# Sensor_Board_A.net
KiCad netlist of a schematic drawn in EAGLE
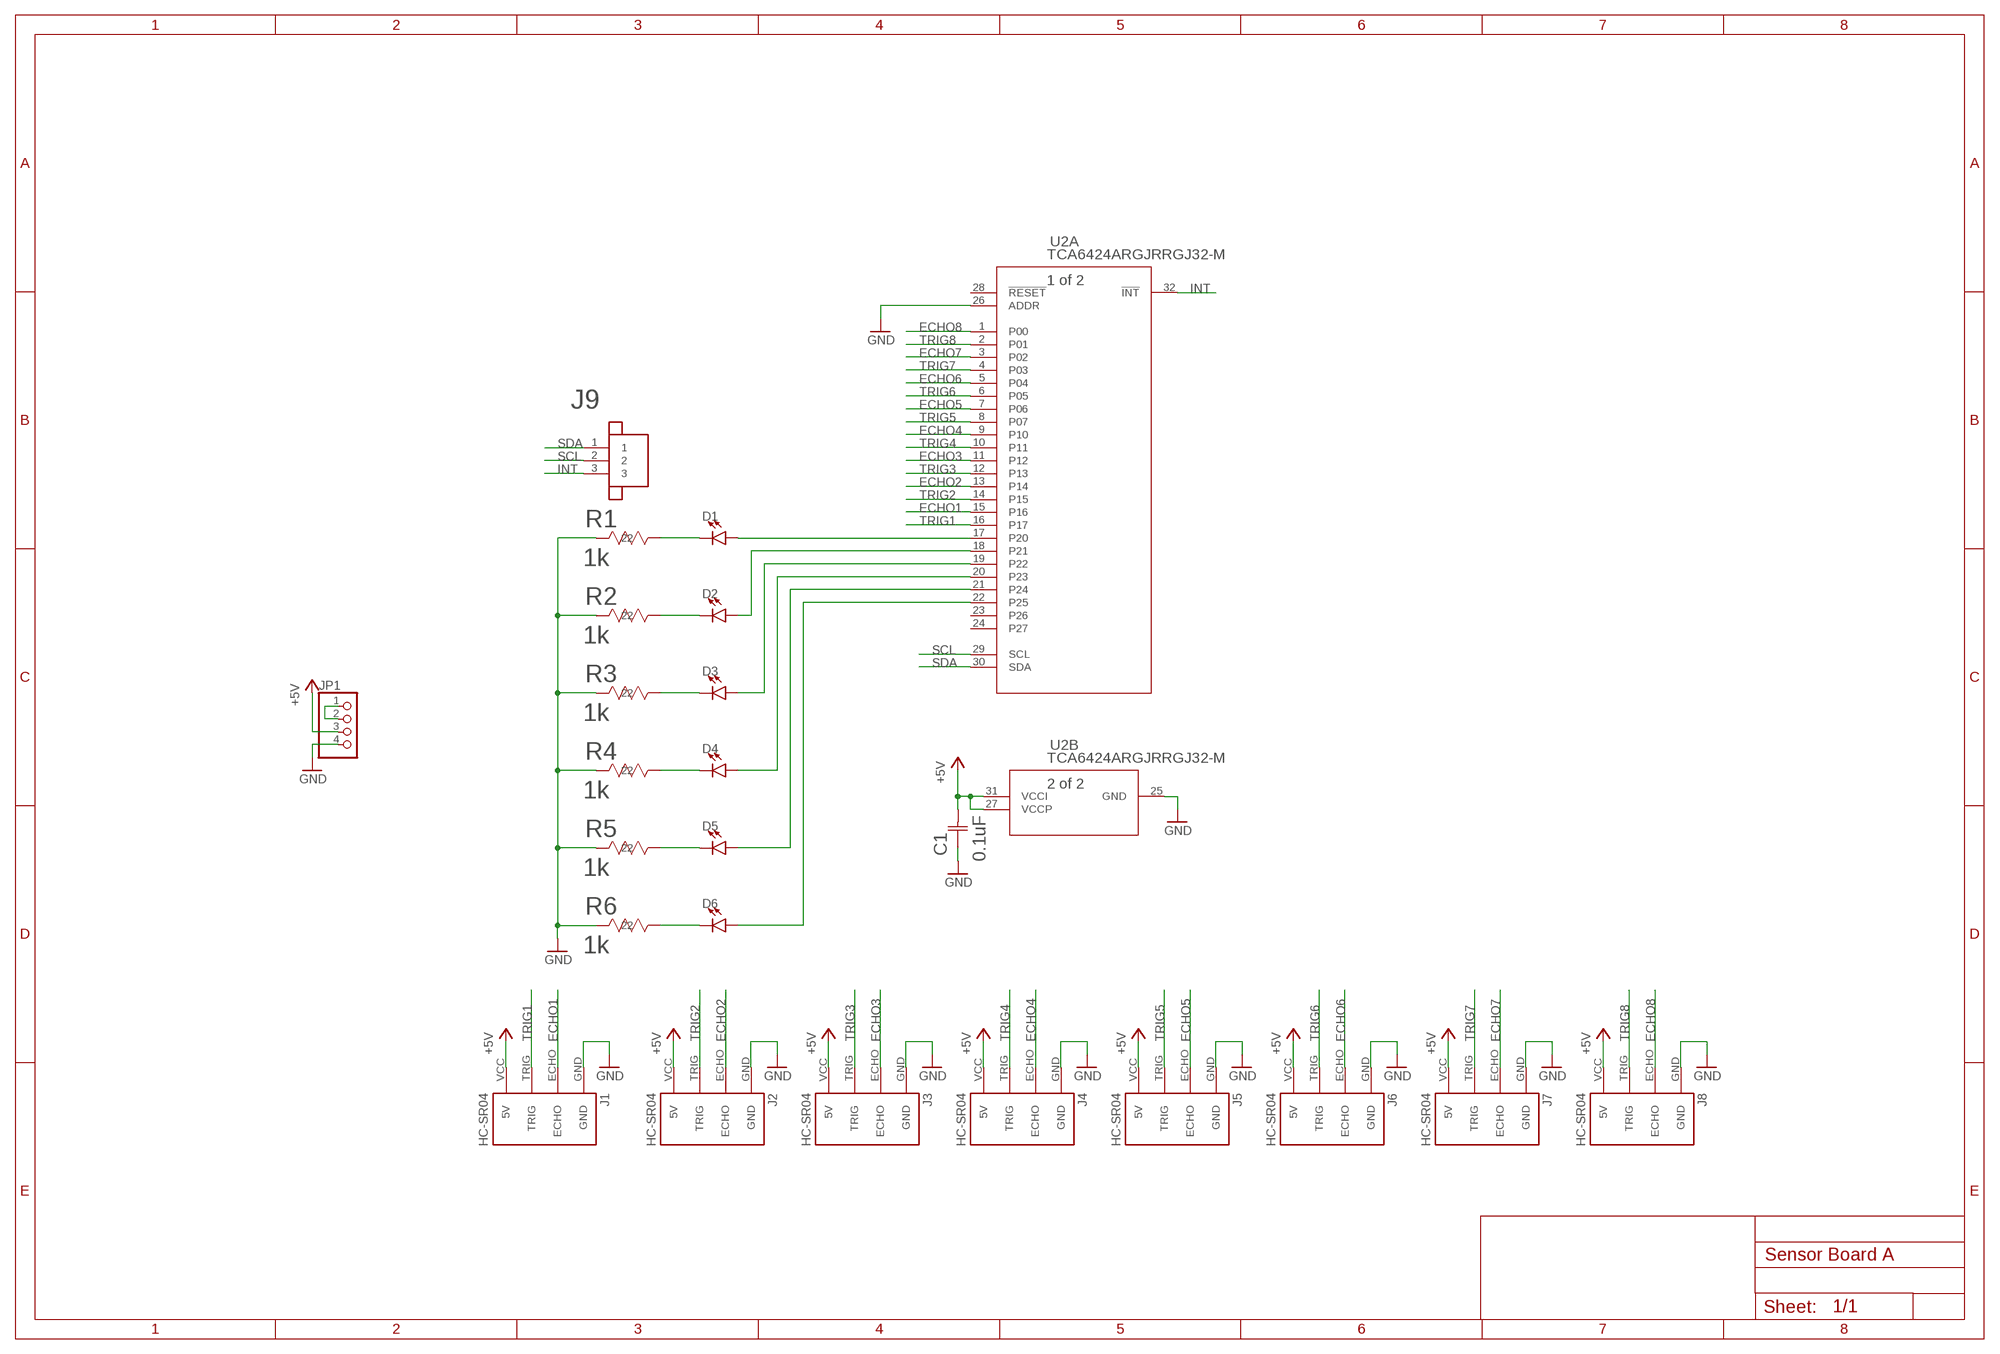
[diagram p0: schematic, sheet 1]

(export (version "E")
  (design (tool "Eeschema 10.0.6"))
  (components
    (comp (ref "C1")
      (value "0.1uF")
      (footprint "eagle-import:0805")
      (fields
        (field (name "MANUFACTURER_PART_NUMBER") "08055C104KAT2A")
        (field (name "COPYRIGHT") "Copyright C 2015 Accelerated Designs. All rights reserved")
      )
      (libsource (lib "eagle-import") (part "08055C104KAT2A"))
    )
    (comp (ref "D1")
      (value "LED0603")
      (footprint "eagle-import:LED-0603")
      (libsource (lib "eagle-import") (part "LED0603"))
    )
    (comp (ref "D2")
      (value "LED0603")
      (footprint "eagle-import:LED-0603")
      (libsource (lib "eagle-import") (part "LED0603"))
    )
    (comp (ref "D3")
      (value "LED0603")
      (footprint "eagle-import:LED-0603")
      (libsource (lib "eagle-import") (part "LED0603"))
    )
    (comp (ref "D4")
      (value "LED0603")
      (footprint "eagle-import:LED-0603")
      (libsource (lib "eagle-import") (part "LED0603"))
    )
    (comp (ref "D5")
      (value "LED0603")
      (footprint "eagle-import:LED-0603")
      (libsource (lib "eagle-import") (part "LED0603"))
    )
    (comp (ref "D6")
      (value "LED0603")
      (footprint "eagle-import:LED-0603")
      (libsource (lib "eagle-import") (part "LED0603"))
    )
    (comp (ref "J1")
      (value "HC-SR04")
      (footprint "eagle-import:HC-SR04_FOOTPRINT")
      (libsource (lib "eagle-import") (part "HC-SR04"))
    )
    (comp (ref "J2")
      (value "HC-SR04")
      (footprint "eagle-import:HC-SR04_FOOTPRINT")
      (libsource (lib "eagle-import") (part "HC-SR04"))
    )
    (comp (ref "J3")
      (value "HC-SR04")
      (footprint "eagle-import:HC-SR04_FOOTPRINT")
      (libsource (lib "eagle-import") (part "HC-SR04"))
    )
    (comp (ref "J4")
      (value "HC-SR04")
      (footprint "eagle-import:HC-SR04_FOOTPRINT")
      (libsource (lib "eagle-import") (part "HC-SR04"))
    )
    (comp (ref "J5")
      (value "HC-SR04")
      (footprint "eagle-import:HC-SR04_FOOTPRINT")
      (libsource (lib "eagle-import") (part "HC-SR04"))
    )
    (comp (ref "J6")
      (value "HC-SR04")
      (footprint "eagle-import:HC-SR04_FOOTPRINT")
      (libsource (lib "eagle-import") (part "HC-SR04"))
    )
    (comp (ref "J7")
      (value "HC-SR04")
      (footprint "eagle-import:HC-SR04_FOOTPRINT")
      (libsource (lib "eagle-import") (part "HC-SR04"))
    )
    (comp (ref "J8")
      (value "HC-SR04")
      (footprint "eagle-import:HC-SR04_FOOTPRINT")
      (libsource (lib "eagle-import") (part "HC-SR04"))
    )
    (comp (ref "J9")
      (value "JST_SH_3POS")
      (footprint "eagle-import:JST_SH_3POS")
      (libsource (lib "eagle-import") (part "JST_SH_3POS"))
    )
    (comp (ref "JP1")
      (value "PINHD-1X4")
      (footprint "eagle-import:1X04")
      (libsource (lib "eagle-import") (part "PINHD-1X4"))
    )
    (comp (ref "R1")
      (value "1k")
      (footprint "eagle-import:RC0603N-M")
      (fields
        (field (name "DIGIKEYPARTNUMBER") "3111.0KGRTRND")
        (field (name "MANUFACTURER_PART_NUMBER") "RC0603JR071KL")
        (field (name "NEWARKPARTNUMBER") "14M7231")
        (field (name "COPYRIGHT") "Copyright C 2015 Accelerated Designs. All rights reserved")
      )
      (libsource (lib "eagle-import") (part "RC0603JR-071KLRC0603N-M"))
    )
    (comp (ref "R2")
      (value "1k")
      (footprint "eagle-import:RC0603N-M")
      (fields
        (field (name "DIGIKEYPARTNUMBER") "3111.0KGRTRND")
        (field (name "MANUFACTURER_PART_NUMBER") "RC0603JR071KL")
        (field (name "NEWARKPARTNUMBER") "14M7231")
        (field (name "COPYRIGHT") "Copyright C 2015 Accelerated Designs. All rights reserved")
      )
      (libsource (lib "eagle-import") (part "RC0603JR-071KLRC0603N-M"))
    )
    (comp (ref "R3")
      (value "1k")
      (footprint "eagle-import:RC0603N-M")
      (fields
        (field (name "DIGIKEYPARTNUMBER") "3111.0KGRTRND")
        (field (name "MANUFACTURER_PART_NUMBER") "RC0603JR071KL")
        (field (name "NEWARKPARTNUMBER") "14M7231")
        (field (name "COPYRIGHT") "Copyright C 2015 Accelerated Designs. All rights reserved")
      )
      (libsource (lib "eagle-import") (part "RC0603JR-071KLRC0603N-M"))
    )
    (comp (ref "R4")
      (value "1k")
      (footprint "eagle-import:RC0603N-M")
      (fields
        (field (name "DIGIKEYPARTNUMBER") "3111.0KGRTRND")
        (field (name "MANUFACTURER_PART_NUMBER") "RC0603JR071KL")
        (field (name "NEWARKPARTNUMBER") "14M7231")
        (field (name "COPYRIGHT") "Copyright C 2015 Accelerated Designs. All rights reserved")
      )
      (libsource (lib "eagle-import") (part "RC0603JR-071KLRC0603N-M"))
    )
    (comp (ref "R5")
      (value "1k")
      (footprint "eagle-import:RC0603N-M")
      (fields
        (field (name "DIGIKEYPARTNUMBER") "3111.0KGRTRND")
        (field (name "MANUFACTURER_PART_NUMBER") "RC0603JR071KL")
        (field (name "NEWARKPARTNUMBER") "14M7231")
        (field (name "COPYRIGHT") "Copyright C 2015 Accelerated Designs. All rights reserved")
      )
      (libsource (lib "eagle-import") (part "RC0603JR-071KLRC0603N-M"))
    )
    (comp (ref "R6")
      (value "1k")
      (footprint "eagle-import:RC0603N-M")
      (fields
        (field (name "DIGIKEYPARTNUMBER") "3111.0KGRTRND")
        (field (name "MANUFACTURER_PART_NUMBER") "RC0603JR071KL")
        (field (name "NEWARKPARTNUMBER") "14M7231")
        (field (name "COPYRIGHT") "Copyright C 2015 Accelerated Designs. All rights reserved")
      )
      (libsource (lib "eagle-import") (part "RC0603JR-071KLRC0603N-M"))
    )
    (comp (ref "U2")
      (value "TCA6424ARGJRRGJ32-M")
      (footprint "eagle-import:RGJ32-M")
      (fields (field (name "MANUFACTURER_PART_NUMBER") "TCA6424ARGJR"))
      (libsource (lib "eagle-import") (part "TCA6424ARGJRRGJ32-M"))
    )
  )
  (nets
    (net (code "1") (name "+5V") (class "Default")
      (node (ref "C1") (pin "2") (pinfunction "2_2") (pintype "passive"))
      (node (ref "J1") (pin "VCC") (pinfunction "5V_VCC") (pintype "bidirectional"))
      (node (ref "J2") (pin "VCC") (pinfunction "5V_VCC") (pintype "bidirectional"))
      (node (ref "J3") (pin "VCC") (pinfunction "5V_VCC") (pintype "bidirectional"))
      (node (ref "J4") (pin "VCC") (pinfunction "5V_VCC") (pintype "bidirectional"))
      (node (ref "J5") (pin "VCC") (pinfunction "5V_VCC") (pintype "bidirectional"))
      (node (ref "J6") (pin "VCC") (pinfunction "5V_VCC") (pintype "bidirectional"))
      (node (ref "J7") (pin "VCC") (pinfunction "5V_VCC") (pintype "bidirectional"))
      (node (ref "J8") (pin "VCC") (pinfunction "5V_VCC") (pintype "bidirectional"))
      (node (ref "JP1") (pin "3") (pinfunction "3_3") (pintype "passive"))
      (node (ref "U2") (pin "27") (pinfunction "VCCP_27") (pintype "power_in"))
      (node (ref "U2") (pin "31") (pinfunction "VCCI_31") (pintype "power_in"))
    )
    (net (code "2") (name "/ECHO1") (class "Default")
      (node (ref "J1") (pin "ECHO") (pinfunction "ECHO_ECHO") (pintype "bidirectional"))
      (node (ref "U2") (pin "15") (pinfunction "P16_15") (pintype "input"))
    )
    (net (code "3") (name "/ECHO2") (class "Default")
      (node (ref "J2") (pin "ECHO") (pinfunction "ECHO_ECHO") (pintype "bidirectional"))
      (node (ref "U2") (pin "13") (pinfunction "P14_13") (pintype "input"))
    )
    (net (code "4") (name "/ECHO3") (class "Default")
      (node (ref "J3") (pin "ECHO") (pinfunction "ECHO_ECHO") (pintype "bidirectional"))
      (node (ref "U2") (pin "11") (pinfunction "P12_11") (pintype "input"))
    )
    (net (code "5") (name "/ECHO4") (class "Default")
      (node (ref "J4") (pin "ECHO") (pinfunction "ECHO_ECHO") (pintype "bidirectional"))
      (node (ref "U2") (pin "9") (pinfunction "P10_9") (pintype "input"))
    )
    (net (code "6") (name "/ECHO5") (class "Default")
      (node (ref "J5") (pin "ECHO") (pinfunction "ECHO_ECHO") (pintype "bidirectional"))
      (node (ref "U2") (pin "7") (pinfunction "P06_7") (pintype "input"))
    )
    (net (code "7") (name "/ECHO6") (class "Default")
      (node (ref "J6") (pin "ECHO") (pinfunction "ECHO_ECHO") (pintype "bidirectional"))
      (node (ref "U2") (pin "5") (pinfunction "P04_5") (pintype "input"))
    )
    (net (code "8") (name "/ECHO7") (class "Default")
      (node (ref "J7") (pin "ECHO") (pinfunction "ECHO_ECHO") (pintype "bidirectional"))
      (node (ref "U2") (pin "3") (pinfunction "P02_3") (pintype "input"))
    )
    (net (code "9") (name "/ECHO8") (class "Default")
      (node (ref "J8") (pin "ECHO") (pinfunction "ECHO_ECHO") (pintype "bidirectional"))
      (node (ref "U2") (pin "1") (pinfunction "P00_1") (pintype "input"))
    )
    (net (code "10") (name "/INT") (class "Default")
      (node (ref "J9") (pin "3") (pinfunction "3_3") (pintype "bidirectional"))
      (node (ref "U2") (pin "32") (pinfunction "~{INT}_32") (pintype "output"))
    )
    (net (code "11") (name "/SCL") (class "Default")
      (node (ref "J9") (pin "2") (pinfunction "2_2") (pintype "bidirectional"))
      (node (ref "U2") (pin "29") (pinfunction "SCL_29") (pintype "passive"))
    )
    (net (code "12") (name "/SDA") (class "Default")
      (node (ref "J9") (pin "1") (pinfunction "1_1") (pintype "bidirectional"))
      (node (ref "U2") (pin "30") (pinfunction "SDA_30") (pintype "passive"))
    )
    (net (code "13") (name "/TRIG1") (class "Default")
      (node (ref "J1") (pin "TRIG") (pinfunction "TRIG_TRIG") (pintype "bidirectional"))
      (node (ref "U2") (pin "16") (pinfunction "P17_16") (pintype "input"))
    )
    (net (code "14") (name "/TRIG2") (class "Default")
      (node (ref "J2") (pin "TRIG") (pinfunction "TRIG_TRIG") (pintype "bidirectional"))
      (node (ref "U2") (pin "14") (pinfunction "P15_14") (pintype "input"))
    )
    (net (code "15") (name "/TRIG3") (class "Default")
      (node (ref "J3") (pin "TRIG") (pinfunction "TRIG_TRIG") (pintype "bidirectional"))
      (node (ref "U2") (pin "12") (pinfunction "P13_12") (pintype "input"))
    )
    (net (code "16") (name "/TRIG4") (class "Default")
      (node (ref "J4") (pin "TRIG") (pinfunction "TRIG_TRIG") (pintype "bidirectional"))
      (node (ref "U2") (pin "10") (pinfunction "P11_10") (pintype "input"))
    )
    (net (code "17") (name "/TRIG5") (class "Default")
      (node (ref "J5") (pin "TRIG") (pinfunction "TRIG_TRIG") (pintype "bidirectional"))
      (node (ref "U2") (pin "8") (pinfunction "P07_8") (pintype "input"))
    )
    (net (code "18") (name "/TRIG6") (class "Default")
      (node (ref "J6") (pin "TRIG") (pinfunction "TRIG_TRIG") (pintype "bidirectional"))
      (node (ref "U2") (pin "6") (pinfunction "P05_6") (pintype "input"))
    )
    (net (code "19") (name "/TRIG7") (class "Default")
      (node (ref "J7") (pin "TRIG") (pinfunction "TRIG_TRIG") (pintype "bidirectional"))
      (node (ref "U2") (pin "4") (pinfunction "P03_4") (pintype "input"))
    )
    (net (code "20") (name "/TRIG8") (class "Default")
      (node (ref "J8") (pin "TRIG") (pinfunction "TRIG_TRIG") (pintype "bidirectional"))
      (node (ref "U2") (pin "2") (pinfunction "P01_2") (pintype "input"))
    )
    (net (code "21") (name "GND") (class "Default")
      (node (ref "C1") (pin "1") (pinfunction "1_1") (pintype "passive"))
      (node (ref "J1") (pin "GND") (pinfunction "GND_GND") (pintype "bidirectional"))
      (node (ref "J2") (pin "GND") (pinfunction "GND_GND") (pintype "bidirectional"))
      (node (ref "J3") (pin "GND") (pinfunction "GND_GND") (pintype "bidirectional"))
      (node (ref "J4") (pin "GND") (pinfunction "GND_GND") (pintype "bidirectional"))
      (node (ref "J5") (pin "GND") (pinfunction "GND_GND") (pintype "bidirectional"))
      (node (ref "J6") (pin "GND") (pinfunction "GND_GND") (pintype "bidirectional"))
      (node (ref "J7") (pin "GND") (pinfunction "GND_GND") (pintype "bidirectional"))
      (node (ref "J8") (pin "GND") (pinfunction "GND_GND") (pintype "bidirectional"))
      (node (ref "JP1") (pin "4") (pinfunction "4_4") (pintype "passive"))
      (node (ref "R1") (pin "2") (pinfunction "22_2") (pintype "passive"))
      (node (ref "R2") (pin "2") (pinfunction "22_2") (pintype "passive"))
      (node (ref "R3") (pin "2") (pinfunction "22_2") (pintype "passive"))
      (node (ref "R4") (pin "2") (pinfunction "22_2") (pintype "passive"))
      (node (ref "R5") (pin "2") (pinfunction "22_2") (pintype "passive"))
      (node (ref "R6") (pin "2") (pinfunction "22_2") (pintype "passive"))
      (node (ref "U2") (pin "25") (pinfunction "GND_25") (pintype "power_in"))
      (node (ref "U2") (pin "26") (pinfunction "ADDR_26") (pintype "input"))
    )
    (net (code "22") (name "Net-(JP1-Pad1)") (class "Default")
      (node (ref "JP1") (pin "1") (pinfunction "1_1") (pintype "passive"))
      (node (ref "JP1") (pin "2") (pinfunction "2_2") (pintype "passive"))
    )
    (net (code "23") (name "Net-(R1-11)") (class "Default")
      (node (ref "D1") (pin "C") (pinfunction "C_C") (pintype "passive"))
      (node (ref "R1") (pin "1") (pinfunction "11_1") (pintype "passive"))
    )
    (net (code "24") (name "Net-(R2-11)") (class "Default")
      (node (ref "D2") (pin "C") (pinfunction "C_C") (pintype "passive"))
      (node (ref "R2") (pin "1") (pinfunction "11_1") (pintype "passive"))
    )
    (net (code "25") (name "Net-(R3-11)") (class "Default")
      (node (ref "D3") (pin "C") (pinfunction "C_C") (pintype "passive"))
      (node (ref "R3") (pin "1") (pinfunction "11_1") (pintype "passive"))
    )
    (net (code "26") (name "Net-(R4-11)") (class "Default")
      (node (ref "D4") (pin "C") (pinfunction "C_C") (pintype "passive"))
      (node (ref "R4") (pin "1") (pinfunction "11_1") (pintype "passive"))
    )
    (net (code "27") (name "Net-(R5-11)") (class "Default")
      (node (ref "D5") (pin "C") (pinfunction "C_C") (pintype "passive"))
      (node (ref "R5") (pin "1") (pinfunction "11_1") (pintype "passive"))
    )
    (net (code "28") (name "Net-(R6-11)") (class "Default")
      (node (ref "D6") (pin "C") (pinfunction "C_C") (pintype "passive"))
      (node (ref "R6") (pin "1") (pinfunction "11_1") (pintype "passive"))
    )
    (net (code "29") (name "Net-(U2A-P20)") (class "Default")
      (node (ref "D1") (pin "A") (pinfunction "A_A") (pintype "passive"))
      (node (ref "U2") (pin "17") (pinfunction "P20_17") (pintype "input"))
    )
    (net (code "30") (name "Net-(U2A-P21)") (class "Default")
      (node (ref "D2") (pin "A") (pinfunction "A_A") (pintype "passive"))
      (node (ref "U2") (pin "18") (pinfunction "P21_18") (pintype "input"))
    )
    (net (code "31") (name "Net-(U2A-P22)") (class "Default")
      (node (ref "D3") (pin "A") (pinfunction "A_A") (pintype "passive"))
      (node (ref "U2") (pin "19") (pinfunction "P22_19") (pintype "input"))
    )
    (net (code "32") (name "Net-(U2A-P23)") (class "Default")
      (node (ref "D4") (pin "A") (pinfunction "A_A") (pintype "passive"))
      (node (ref "U2") (pin "20") (pinfunction "P23_20") (pintype "input"))
    )
    (net (code "33") (name "Net-(U2A-P24)") (class "Default")
      (node (ref "D5") (pin "A") (pinfunction "A_A") (pintype "passive"))
      (node (ref "U2") (pin "21") (pinfunction "P24_21") (pintype "input"))
    )
    (net (code "34") (name "Net-(U2A-P25)") (class "Default")
      (node (ref "D6") (pin "A") (pinfunction "A_A") (pintype "passive"))
      (node (ref "U2") (pin "22") (pinfunction "P25_22") (pintype "input"))
    )
    (net (code "35") (name "unconnected-(U2A-P26-Pad23)") (class "Default")
      (node (ref "U2") (pin "23") (pinfunction "P26_23") (pintype "input"))
    )
    (net (code "36") (name "unconnected-(U2A-P27-Pad24)") (class "Default")
      (node (ref "U2") (pin "24") (pinfunction "P27_24") (pintype "input"))
    )
    (net (code "37") (name "unconnected-(U2A-~{RESET}-Pad28)") (class "Default")
      (node (ref "U2") (pin "28") (pinfunction "~{RESET}_28") (pintype "input"))
    )
  )
)
